# Supply_5V_to_3V3-_Ams1117.net
KiCad netlist of a schematic drawn in Altium Designer
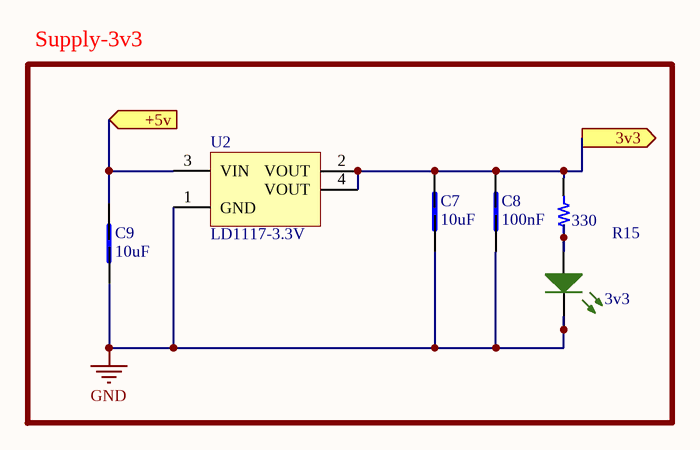
[diagram p0: Supply 5V to 3V3- Ams1117.SchDoc]

(export (version "E")
  (design (tool "Eeschema 10.0.6"))
  (components
    (comp (ref "3v3")
      (value "LED SMD 0805 GREEN")
      (footprint "LED_0805_GREEN")
      (libsource (lib "Led") (part "LED SMD 0805 GREEN"))
    )
    (comp (ref "C7")
      (value "10uF")
      (footprint "CAP 0805_2012")
      (description "COMMERCIAL CHIP STD JAPAN BULK - FN TAPE/REEL, 7 INCH PAPER TAPE-0805")
      (fields (field (name "MP") "LD051C182KAB2A"))
      (libsource (lib "cap 0805") (part "LD051C182KAB2A"))
    )
    (comp (ref "C8")
      (value "100nF")
      (footprint "CAP 0805_2012")
      (description "COMMERCIAL CHIP STD JAPAN BULK - FN TAPE/REEL, 7 INCH PAPER TAPE-0805")
      (fields (field (name "MP") "LD051C182KAB2A"))
      (libsource (lib "cap 0805") (part "LD051C182KAB2A"))
    )
    (comp (ref "C9")
      (value "10uF")
      (footprint "CAP 0805_2012")
      (description "COMMERCIAL CHIP STD JAPAN BULK - FN TAPE/REEL, 7 INCH PAPER TAPE-0805")
      (fields (field (name "MP") "LD051C182KAB2A"))
      (libsource (lib "cap 0805") (part "LD051C182KAB2A"))
    )
    (comp (ref "R15")
      (value "330")
      (footprint "RES 0805_2012")
      (description "SMT Resistor")
      (libsource (lib "Resistor") (part "Res 0805"))
    )
    (comp (ref "U2")
      (value "LD1117-3.3V")
      (footprint "SOT-223-4 6.5X7MM P2.3MM")
      (description "Linear Voltage Regulator IC  1 Output  800mA SOT-223")
      (fields (field (name "PARTNUMBER") "LD1117S33CTR"))
      (libsource (lib "Chip") (part "LD1117-3.3V (SMD SOT-223)"))
    )
  )
  (nets
    (net (code "1") (name "/+5v") (class "Default")
      (node (ref "C9") (pin "2") (pinfunction "2_2") (pintype "passive"))
      (node (ref "U2") (pin "3") (pinfunction "VIN_3") (pintype "passive"))
    )
    (net (code "2") (name "/3v3") (class "Default")
      (node (ref "C7") (pin "2") (pinfunction "2_2") (pintype "passive"))
      (node (ref "C8") (pin "2") (pinfunction "2_2") (pintype "passive"))
      (node (ref "R15") (pin "1") (pinfunction "1_1") (pintype "passive"))
      (node (ref "U2") (pin "2") (pinfunction "VOUT_2") (pintype "passive"))
      (node (ref "U2") (pin "4") (pinfunction "VOUT_4") (pintype "passive"))
    )
    (net (code "3") (name "GND") (class "Default")
      (node (ref "3v3") (pin "2") (pinfunction "K_2") (pintype "passive"))
      (node (ref "C7") (pin "1") (pinfunction "1_1") (pintype "passive"))
      (node (ref "C8") (pin "1") (pinfunction "1_1") (pintype "passive"))
      (node (ref "C9") (pin "1") (pinfunction "1_1") (pintype "passive"))
      (node (ref "U2") (pin "1") (pinfunction "GND_1") (pintype "passive"))
    )
    (net (code "4") (name "Net-(3v3-A)") (class "Default")
      (node (ref "3v3") (pin "1") (pinfunction "A_1") (pintype "passive"))
      (node (ref "R15") (pin "2") (pinfunction "2_2") (pintype "passive"))
    )
  )
)
